# Daughter2.net
KiCad netlist of a schematic drawn in EAGLE
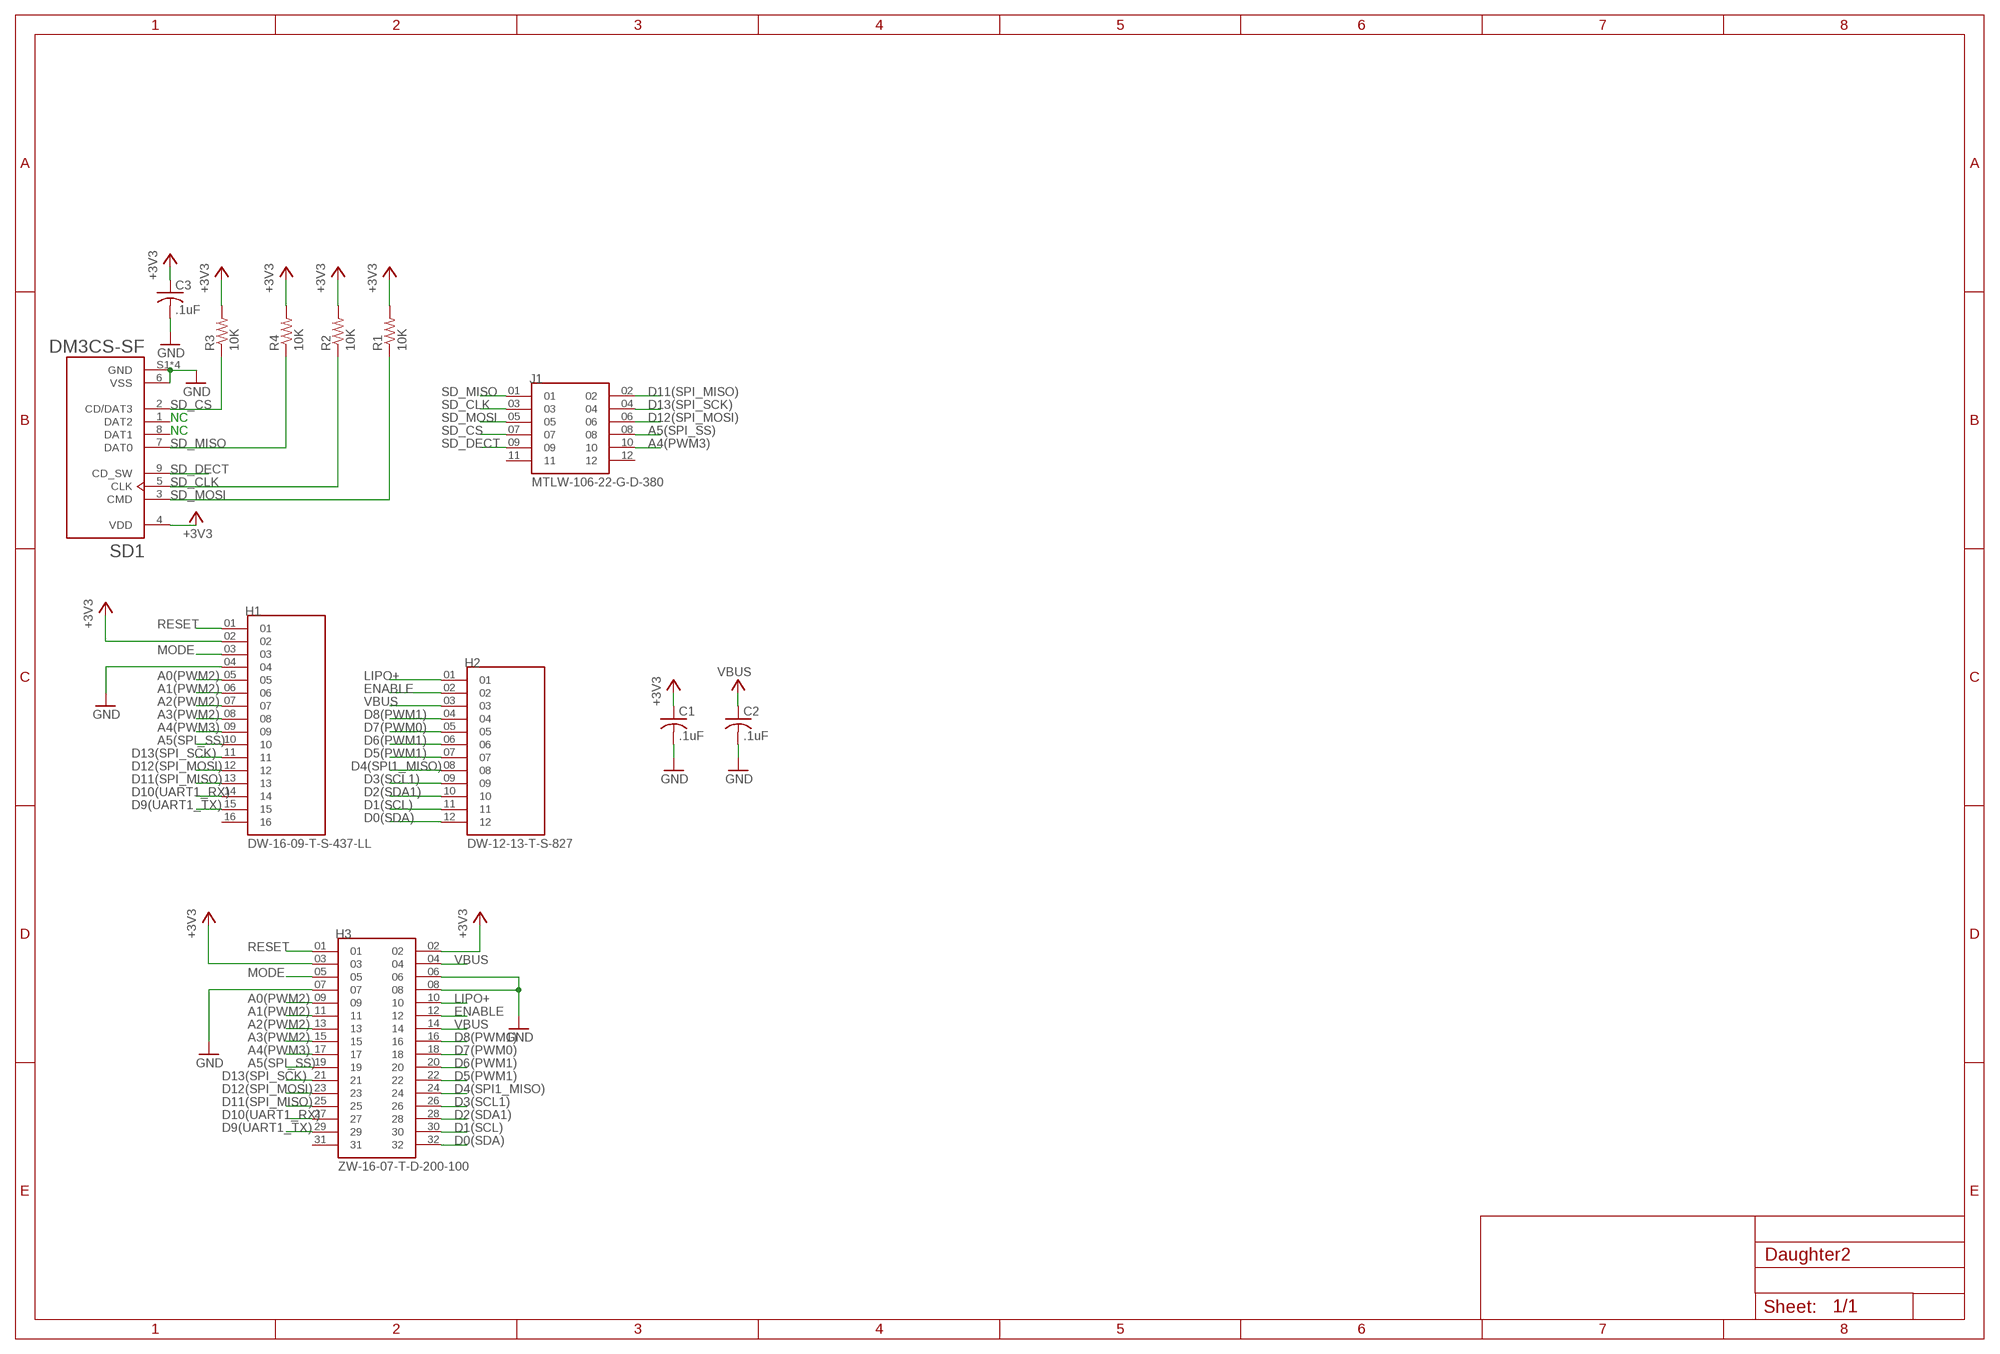
[diagram p0: schematic, sheet 1]

(export (version "E")
  (design (tool "Eeschema 10.0.6"))
  (components
    (comp (ref "C1")
      (value ".1uF")
      (footprint "eagle-import:C0805")
      (libsource (lib "eagle-import") (part "C-USC0805"))
    )
    (comp (ref "C2")
      (value ".1uF")
      (footprint "eagle-import:C0805")
      (libsource (lib "eagle-import") (part "C-USC0805"))
    )
    (comp (ref "C3")
      (value ".1uF")
      (footprint "eagle-import:C0805")
      (libsource (lib "eagle-import") (part "C-USC0805"))
    )
    (comp (ref "H1")
      (value "DW-16-09-T-S-437-LL")
      (footprint "eagle-import:SAMTEC_DW-16-09-T-S-437-LL")
      (fields (field (name "MF") "Samtec"))
      (libsource (lib "eagle-import") (part "DW-16-09-T-S-437-LL"))
    )
    (comp (ref "H2")
      (value "DW-12-13-T-S-827")
      (footprint "eagle-import:SAMTEC_DW-12-13-T-S-827")
      (fields (field (name "MF") "Samtec Inc."))
      (libsource (lib "eagle-import") (part "DW-12-13-T-S-827"))
    )
    (comp (ref "H3")
      (value "ZW-16-07-T-D-200-100")
      (footprint "eagle-import:SAMTEC_ZW-16-07-T-D-200-100")
      (fields (field (name "MF") "Samtec Inc."))
      (libsource (lib "eagle-import") (part "ZW-16-07-T-D-200-100"))
    )
    (comp (ref "J1")
      (value "MTLW-106-22-G-D-380")
      (footprint "eagle-import:SAMTEC_MTLW-106-22-G-D-380")
      (fields (field (name "MF") "Samtec"))
      (libsource (lib "eagle-import") (part "MTLW-106-22-G-D-380"))
    )
    (comp (ref "R1")
      (value "10K")
      (footprint "eagle-import:R0805")
      (libsource (lib "eagle-import") (part "R-US_R0805"))
    )
    (comp (ref "R2")
      (value "10K")
      (footprint "eagle-import:R0805")
      (libsource (lib "eagle-import") (part "R-US_R0805"))
    )
    (comp (ref "R3")
      (value "10K")
      (footprint "eagle-import:R0805")
      (libsource (lib "eagle-import") (part "R-US_R0805"))
    )
    (comp (ref "R4")
      (value "10K")
      (footprint "eagle-import:R0805")
      (libsource (lib "eagle-import") (part "R-US_R0805"))
    )
    (comp (ref "SD1")
      (value "DM3CS-SF")
      (footprint "eagle-import:HRS_DM3CS-SF")
      (fields (field (name "MF") "Hirose"))
      (libsource (lib "eagle-import") (part "DM3CS-SF"))
    )
  )
  (nets
    (net (code "1") (name "+3V3") (class "Default")
      (node (ref "C1") (pin "1") (pinfunction "1_1") (pintype "passive"))
      (node (ref "C3") (pin "1") (pinfunction "1_1") (pintype "passive"))
      (node (ref "H1") (pin "02") (pinfunction "02_02") (pintype "passive"))
      (node (ref "H3") (pin "02") (pinfunction "02_02") (pintype "passive"))
      (node (ref "H3") (pin "03") (pinfunction "03_03") (pintype "passive"))
      (node (ref "R1") (pin "2") (pinfunction "2_2") (pintype "passive"))
      (node (ref "R2") (pin "2") (pinfunction "2_2") (pintype "passive"))
      (node (ref "R3") (pin "2") (pinfunction "2_2") (pintype "passive"))
      (node (ref "R4") (pin "2") (pinfunction "2_2") (pintype "passive"))
      (node (ref "SD1") (pin "4") (pinfunction "VDD_4") (pintype "passive"))
    )
    (net (code "2") (name "/A0(PWM2)") (class "Default")
      (node (ref "H1") (pin "05") (pinfunction "05_05") (pintype "passive"))
      (node (ref "H3") (pin "09") (pinfunction "09_09") (pintype "passive"))
    )
    (net (code "3") (name "/A1(PWM2)") (class "Default")
      (node (ref "H1") (pin "06") (pinfunction "06_06") (pintype "passive"))
      (node (ref "H3") (pin "11") (pinfunction "11_11") (pintype "passive"))
    )
    (net (code "4") (name "/A2(PWM2)") (class "Default")
      (node (ref "H1") (pin "07") (pinfunction "07_07") (pintype "passive"))
      (node (ref "H3") (pin "13") (pinfunction "13_13") (pintype "passive"))
    )
    (net (code "5") (name "/A3(PWM2)") (class "Default")
      (node (ref "H1") (pin "08") (pinfunction "08_08") (pintype "passive"))
      (node (ref "H3") (pin "15") (pinfunction "15_15") (pintype "passive"))
    )
    (net (code "6") (name "/A4(PWM3)") (class "Default")
      (node (ref "H1") (pin "09") (pinfunction "09_09") (pintype "passive"))
      (node (ref "H3") (pin "17") (pinfunction "17_17") (pintype "passive"))
      (node (ref "J1") (pin "10") (pinfunction "10_10") (pintype "passive"))
    )
    (net (code "7") (name "/A5(SPI_SS)") (class "Default")
      (node (ref "H1") (pin "10") (pinfunction "10_10") (pintype "passive"))
      (node (ref "H3") (pin "19") (pinfunction "19_19") (pintype "passive"))
      (node (ref "J1") (pin "08") (pinfunction "08_08") (pintype "passive"))
    )
    (net (code "8") (name "/D0(SDA)") (class "Default")
      (node (ref "H2") (pin "12") (pinfunction "12_12") (pintype "passive"))
      (node (ref "H3") (pin "32") (pinfunction "32_32") (pintype "passive"))
    )
    (net (code "9") (name "/D1(SCL)") (class "Default")
      (node (ref "H2") (pin "11") (pinfunction "11_11") (pintype "passive"))
      (node (ref "H3") (pin "30") (pinfunction "30_30") (pintype "passive"))
    )
    (net (code "10") (name "/D2(SDA1)") (class "Default")
      (node (ref "H2") (pin "10") (pinfunction "10_10") (pintype "passive"))
      (node (ref "H3") (pin "28") (pinfunction "28_28") (pintype "passive"))
    )
    (net (code "11") (name "/D3(SCL1)") (class "Default")
      (node (ref "H2") (pin "09") (pinfunction "09_09") (pintype "passive"))
      (node (ref "H3") (pin "26") (pinfunction "26_26") (pintype "passive"))
    )
    (net (code "12") (name "/D4(SPI1_MISO)") (class "Default")
      (node (ref "H2") (pin "08") (pinfunction "08_08") (pintype "passive"))
      (node (ref "H3") (pin "24") (pinfunction "24_24") (pintype "passive"))
    )
    (net (code "13") (name "/D5(PWM1)") (class "Default")
      (node (ref "H2") (pin "07") (pinfunction "07_07") (pintype "passive"))
      (node (ref "H3") (pin "22") (pinfunction "22_22") (pintype "passive"))
    )
    (net (code "14") (name "/D6(PWM1)") (class "Default")
      (node (ref "H2") (pin "06") (pinfunction "06_06") (pintype "passive"))
      (node (ref "H3") (pin "20") (pinfunction "20_20") (pintype "passive"))
    )
    (net (code "15") (name "/D7(PWM0)") (class "Default")
      (node (ref "H2") (pin "05") (pinfunction "05_05") (pintype "passive"))
      (node (ref "H3") (pin "18") (pinfunction "18_18") (pintype "passive"))
    )
    (net (code "16") (name "/D8(PWM1)") (class "Default")
      (node (ref "H2") (pin "04") (pinfunction "04_04") (pintype "passive"))
      (node (ref "H3") (pin "16") (pinfunction "16_16") (pintype "passive"))
    )
    (net (code "17") (name "/D9(UART1_TX)") (class "Default")
      (node (ref "H1") (pin "15") (pinfunction "15_15") (pintype "passive"))
      (node (ref "H3") (pin "29") (pinfunction "29_29") (pintype "passive"))
    )
    (net (code "18") (name "/D10(UART1_RX)") (class "Default")
      (node (ref "H1") (pin "14") (pinfunction "14_14") (pintype "passive"))
      (node (ref "H3") (pin "27") (pinfunction "27_27") (pintype "passive"))
    )
    (net (code "19") (name "/D11(SPI_MISO)") (class "Default")
      (node (ref "H1") (pin "13") (pinfunction "13_13") (pintype "passive"))
      (node (ref "H3") (pin "25") (pinfunction "25_25") (pintype "passive"))
      (node (ref "J1") (pin "02") (pinfunction "02_02") (pintype "passive"))
    )
    (net (code "20") (name "/D12(SPI_MOSI)") (class "Default")
      (node (ref "H1") (pin "12") (pinfunction "12_12") (pintype "passive"))
      (node (ref "H3") (pin "23") (pinfunction "23_23") (pintype "passive"))
      (node (ref "J1") (pin "06") (pinfunction "06_06") (pintype "passive"))
    )
    (net (code "21") (name "/D13(SPI_SCK)") (class "Default")
      (node (ref "H1") (pin "11") (pinfunction "11_11") (pintype "passive"))
      (node (ref "H3") (pin "21") (pinfunction "21_21") (pintype "passive"))
      (node (ref "J1") (pin "04") (pinfunction "04_04") (pintype "passive"))
    )
    (net (code "22") (name "/ENABLE") (class "Default")
      (node (ref "H2") (pin "02") (pinfunction "02_02") (pintype "passive"))
      (node (ref "H3") (pin "12") (pinfunction "12_12") (pintype "passive"))
    )
    (net (code "23") (name "/LIPO+") (class "Default")
      (node (ref "H2") (pin "01") (pinfunction "01_01") (pintype "passive"))
      (node (ref "H3") (pin "10") (pinfunction "10_10") (pintype "passive"))
    )
    (net (code "24") (name "/MODE") (class "Default")
      (node (ref "H1") (pin "03") (pinfunction "03_03") (pintype "passive"))
      (node (ref "H3") (pin "05") (pinfunction "05_05") (pintype "passive"))
    )
    (net (code "25") (name "/RESET") (class "Default")
      (node (ref "H1") (pin "01") (pinfunction "01_01") (pintype "passive"))
      (node (ref "H3") (pin "01") (pinfunction "01_01") (pintype "passive"))
    )
    (net (code "26") (name "/SD_CLK") (class "Default")
      (node (ref "J1") (pin "03") (pinfunction "03_03") (pintype "passive"))
      (node (ref "R2") (pin "1") (pinfunction "1_1") (pintype "passive"))
      (node (ref "SD1") (pin "5") (pinfunction "CLK_5") (pintype "passive"))
    )
    (net (code "27") (name "/SD_CS") (class "Default")
      (node (ref "J1") (pin "07") (pinfunction "07_07") (pintype "passive"))
      (node (ref "R3") (pin "1") (pinfunction "1_1") (pintype "passive"))
      (node (ref "SD1") (pin "2") (pinfunction "CD/DAT3_2") (pintype "passive"))
    )
    (net (code "28") (name "/SD_DECT") (class "Default")
      (node (ref "J1") (pin "09") (pinfunction "09_09") (pintype "passive"))
      (node (ref "SD1") (pin "9") (pinfunction "CD_SW_9") (pintype "passive"))
    )
    (net (code "29") (name "/SD_MISO") (class "Default")
      (node (ref "J1") (pin "01") (pinfunction "01_01") (pintype "passive"))
      (node (ref "R4") (pin "1") (pinfunction "1_1") (pintype "passive"))
      (node (ref "SD1") (pin "7") (pinfunction "DAT0_7") (pintype "passive"))
    )
    (net (code "30") (name "/SD_MOSI") (class "Default")
      (node (ref "J1") (pin "05") (pinfunction "05_05") (pintype "passive"))
      (node (ref "R1") (pin "1") (pinfunction "1_1") (pintype "passive"))
      (node (ref "SD1") (pin "3") (pinfunction "CMD_3") (pintype "passive"))
    )
    (net (code "31") (name "GND") (class "Default")
      (node (ref "C1") (pin "2") (pinfunction "2_2") (pintype "passive"))
      (node (ref "C2") (pin "2") (pinfunction "2_2") (pintype "passive"))
      (node (ref "C3") (pin "2") (pinfunction "2_2") (pintype "passive"))
      (node (ref "H1") (pin "04") (pinfunction "04_04") (pintype "passive"))
      (node (ref "H3") (pin "06") (pinfunction "06_06") (pintype "passive"))
      (node (ref "H3") (pin "07") (pinfunction "07_07") (pintype "passive"))
      (node (ref "H3") (pin "08") (pinfunction "08_08") (pintype "passive"))
      (node (ref "SD1") (pin "6") (pinfunction "VSS_6") (pintype "passive"))
      (node (ref "SD1") (pin "S1") (pinfunction "GND_S1") (pintype "passive"))
      (node (ref "SD1") (pin "S2") (pinfunction "GND_S2") (pintype "passive"))
      (node (ref "SD1") (pin "S3") (pinfunction "GND_S3") (pintype "passive"))
      (node (ref "SD1") (pin "S5") (pinfunction "GND_S5") (pintype "passive"))
    )
    (net (code "32") (name "VCC") (class "Default")
      (node (ref "C2") (pin "1") (pinfunction "1_1") (pintype "passive"))
      (node (ref "H2") (pin "03") (pinfunction "03_03") (pintype "passive"))
      (node (ref "H3") (pin "04") (pinfunction "04_04") (pintype "passive"))
      (node (ref "H3") (pin "14") (pinfunction "14_14") (pintype "passive"))
    )
    (net (code "33") (name "unconnected-(H1-Pad16)") (class "Default")
      (node (ref "H1") (pin "16") (pinfunction "16_16") (pintype "passive"))
    )
    (net (code "34") (name "unconnected-(H3-Pad31)") (class "Default")
      (node (ref "H3") (pin "31") (pinfunction "31_31") (pintype "passive"))
    )
    (net (code "35") (name "unconnected-(J1-Pad11)") (class "Default")
      (node (ref "J1") (pin "11") (pinfunction "11_11") (pintype "passive"))
    )
    (net (code "36") (name "unconnected-(J1-Pad12)") (class "Default")
      (node (ref "J1") (pin "12") (pinfunction "12_12") (pintype "passive"))
    )
    (net (code "37") (name "unconnected-(SD1-DAT1-Pad8)") (class "Default")
      (node (ref "SD1") (pin "8") (pinfunction "DAT1_8") (pintype "passive"))
    )
    (net (code "38") (name "unconnected-(SD1-DAT2-Pad1)") (class "Default")
      (node (ref "SD1") (pin "1") (pinfunction "DAT2_1") (pintype "passive"))
    )
  )
)
